# mic.net
KiCad netlist of a schematic drawn in Altium Designer
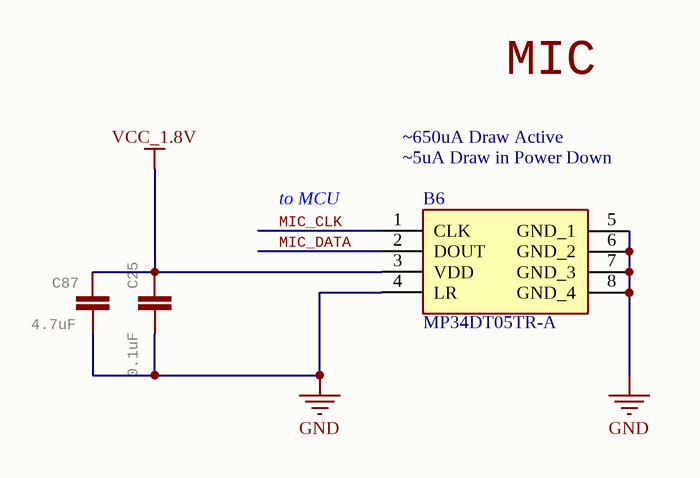
[diagram p0: mic.SchDoc]

(export (version "E")
  (design (tool "Eeschema 10.0.6"))
  (components
    (comp (ref "B6")
      (value "MP34DT05TR-A")
      (footprint "MP34DT05TRA")
      (description "STMICROELECTRONICS - MP34DT05TR-A - MEMS MICROPHONE, 3.6V, HCLGA-4")
      (fields (field (name "MOUSER PART NUMBER") "511-MP34DT05TR-A"))
      (libsource (lib "openmv-ae3") (part "MP34DT05TR-A"))
    )
    (comp (ref "C25")
      (value "0.1uF")
      (footprint "0402-CAP")
      (description "CAPACITOR, European symbol")
      (fields (field (name "MPN") "C0402C104Z4VAC"))
      (libsource (lib "openmv-ae3") (part "C-EUC0201"))
    )
    (comp (ref "C87")
      (value "4.7uF")
      (footprint "0402-CAP")
      (description "CapacitorStandard 0603 ceramic capacitor, and 0.1\" leaded capacitor.")
      (fields (field (name "MPN") "JMK105BBJ475MV-F") (field (name "LIBRARYNAME") "sfe"))
      (libsource (lib "openmv-ae3") (part "CAP0402-CAP"))
    )
  )
  (nets
    (net (code "1") (name "/MIC_CLK") (class "Default")
      (node (ref "B6") (pin "1") (pinfunction "CLK_1") (pintype "passive"))
    )
    (net (code "2") (name "/MIC_DATA") (class "Default")
      (node (ref "B6") (pin "2") (pinfunction "DOUT_2") (pintype "passive"))
    )
    (net (code "3") (name "GND") (class "Default")
      (node (ref "B6") (pin "4") (pinfunction "LR_4") (pintype "passive"))
      (node (ref "B6") (pin "5") (pinfunction "GND_1_5") (pintype "passive"))
      (node (ref "B6") (pin "6") (pinfunction "GND_2_6") (pintype "passive"))
      (node (ref "B6") (pin "7") (pinfunction "GND_3_7") (pintype "passive"))
      (node (ref "B6") (pin "8") (pinfunction "GND_4_8") (pintype "passive"))
      (node (ref "C25") (pin "2") (pinfunction "2_2") (pintype "passive"))
      (node (ref "C87") (pin "1") (pinfunction "1_1") (pintype "passive"))
    )
    (net (code "4") (name "VCC_1.8V") (class "Default")
      (node (ref "B6") (pin "3") (pinfunction "VDD_3") (pintype "passive"))
      (node (ref "C25") (pin "1") (pinfunction "1_1") (pintype "passive"))
      (node (ref "C87") (pin "2") (pinfunction "2_2") (pintype "passive"))
    )
  )
)
